# dev_board.net
KiCad netlist of a schematic drawn in EAGLE
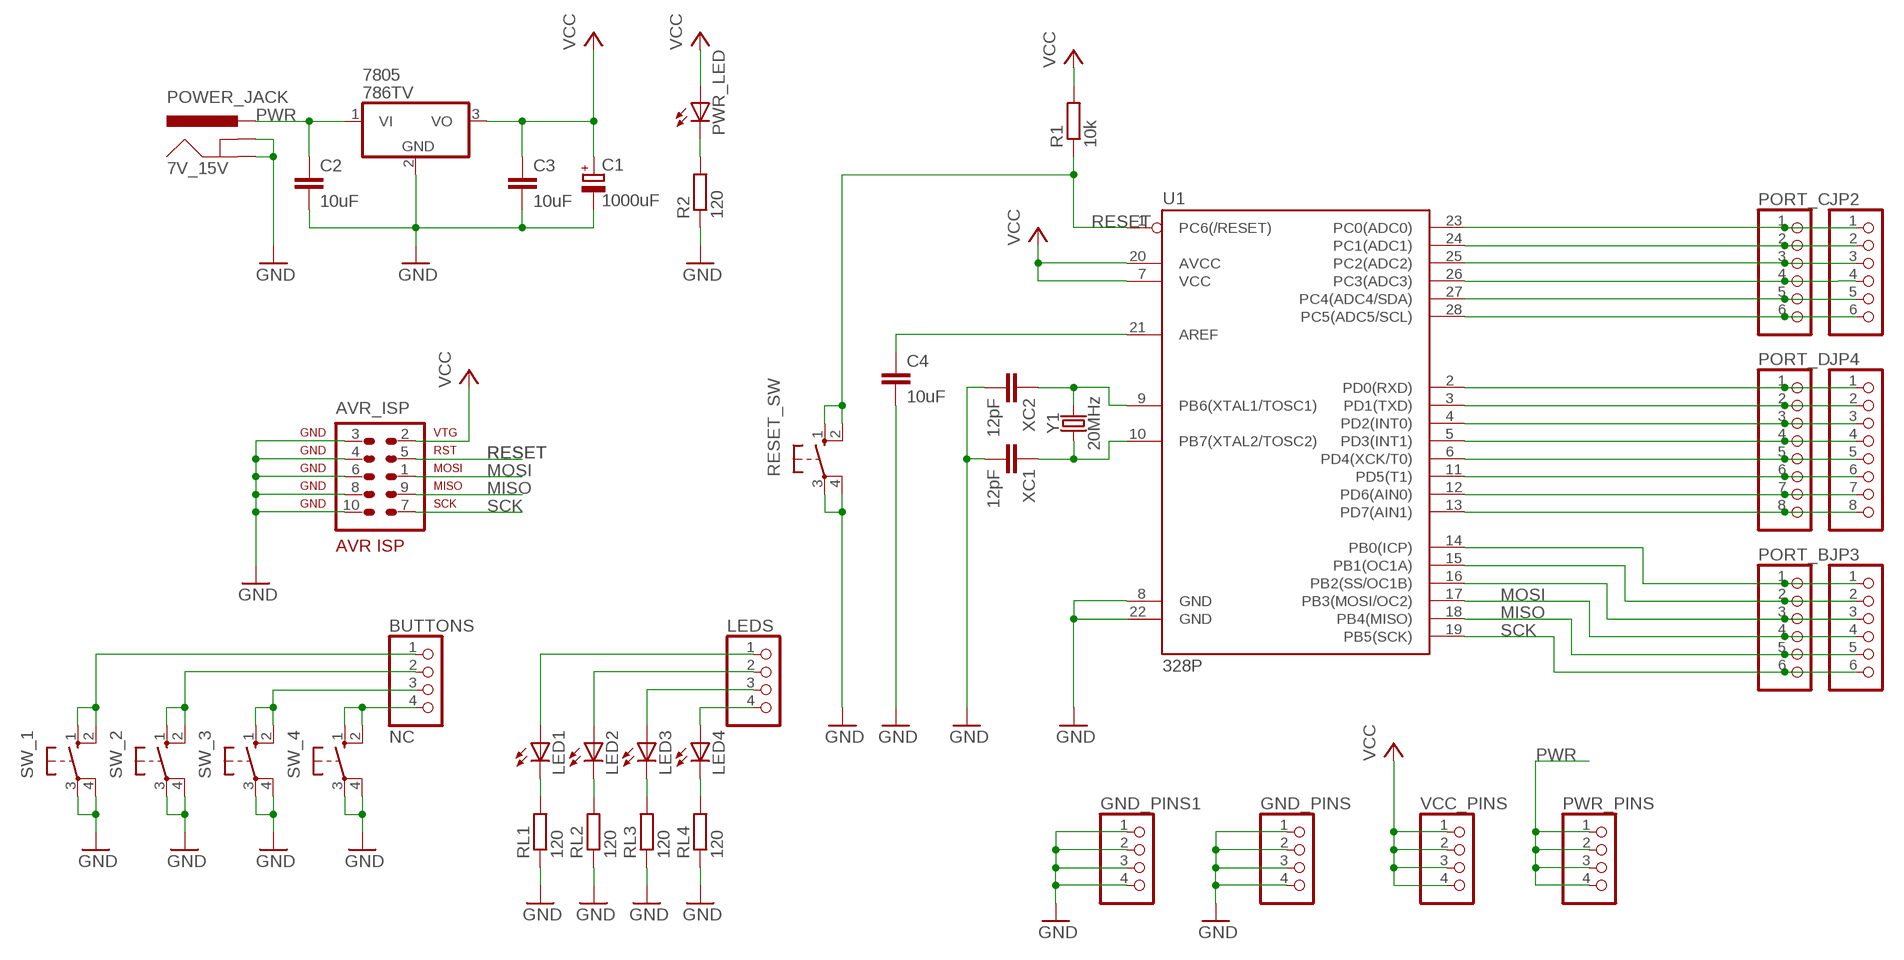
[diagram p0: schematic, sheet 1]

(export (version "E")
  (design (tool "Eeschema 10.0.6"))
  (components
    (comp (ref "7V_15V")
      (value "POWER_JACK")
      (footprint "eagle-import:POWER_JACK_PTH")
      (libsource (lib "eagle-import") (part "POWER_JACK"))
    )
    (comp (ref "7805")
      (value "786TV")
      (footprint "eagle-import:TO220V")
      (libsource (lib "eagle-import") (part "78TV6"))
    )
    (comp (ref "AVR_ISP")
      (value "AVR-ISP-10")
      (footprint "eagle-import:AVR-ISP-10")
      (libsource (lib "eagle-import") (part "AVR-ISP-10"))
    )
    (comp (ref "BUTTONS")
      (value "NC")
      (footprint "eagle-import:1X04")
      (libsource (lib "eagle-import") (part "PINHD-1X4"))
    )
    (comp (ref "C1")
      (value "1000uF")
      (footprint "eagle-import:E3,5-10")
      (libsource (lib "eagle-import") (part "CPOL-EUE3.5-10"))
    )
    (comp (ref "C2")
      (value "10uF")
      (footprint "eagle-import:C025-025X050")
      (libsource (lib "eagle-import") (part "C-EU025-025X050"))
    )
    (comp (ref "C3")
      (value "10uF")
      (footprint "eagle-import:C025-025X050")
      (libsource (lib "eagle-import") (part "C-EU025-025X050"))
    )
    (comp (ref "C4")
      (value "10uF")
      (footprint "eagle-import:C025-025X050")
      (libsource (lib "eagle-import") (part "C-EU025-025X050"))
    )
    (comp (ref "GND_PINS")
      (value "PINHD-1X4")
      (footprint "eagle-import:1X04")
      (libsource (lib "eagle-import") (part "PINHD-1X4"))
    )
    (comp (ref "GND_PINS1")
      (value "PINHD-1X4")
      (footprint "eagle-import:1X04")
      (libsource (lib "eagle-import") (part "PINHD-1X4"))
    )
    (comp (ref "JP2")
      (value "PINHD-1X6")
      (footprint "eagle-import:1X06")
      (libsource (lib "eagle-import") (part "PINHD-1X6"))
    )
    (comp (ref "JP3")
      (value "PINHD-1X6")
      (footprint "eagle-import:1X06")
      (libsource (lib "eagle-import") (part "PINHD-1X6"))
    )
    (comp (ref "JP4")
      (value "PINHD-1X8")
      (footprint "eagle-import:1X08")
      (libsource (lib "eagle-import") (part "PINHD-1X8"))
    )
    (comp (ref "LED1")
      (value "LED5MM")
      (footprint "eagle-import:LED5MM")
      (libsource (lib "eagle-import") (part "LED5MM"))
    )
    (comp (ref "LED2")
      (value "LED5MM")
      (footprint "eagle-import:LED5MM")
      (libsource (lib "eagle-import") (part "LED5MM"))
    )
    (comp (ref "LED3")
      (value "LED5MM")
      (footprint "eagle-import:LED5MM")
      (libsource (lib "eagle-import") (part "LED5MM"))
    )
    (comp (ref "LED4")
      (value "LED5MM")
      (footprint "eagle-import:LED5MM")
      (libsource (lib "eagle-import") (part "LED5MM"))
    )
    (comp (ref "LEDS")
      (value "PINHD-1X4")
      (footprint "eagle-import:1X04")
      (libsource (lib "eagle-import") (part "PINHD-1X4"))
    )
    (comp (ref "PORT_B")
      (value "PINHD-1X6")
      (footprint "eagle-import:1X06")
      (libsource (lib "eagle-import") (part "PINHD-1X6"))
    )
    (comp (ref "PORT_C")
      (value "PINHD-1X6")
      (footprint "eagle-import:1X06")
      (libsource (lib "eagle-import") (part "PINHD-1X6"))
    )
    (comp (ref "PORT_D")
      (value "PINHD-1X8")
      (footprint "eagle-import:1X08")
      (libsource (lib "eagle-import") (part "PINHD-1X8"))
    )
    (comp (ref "PWR_LED")
      (value "LED3MM")
      (footprint "eagle-import:LED3MM")
      (libsource (lib "eagle-import") (part "LED3MM"))
    )
    (comp (ref "PWR_PINS")
      (value "PINHD-1X4")
      (footprint "eagle-import:1X04")
      (libsource (lib "eagle-import") (part "PINHD-1X4"))
    )
    (comp (ref "R1")
      (value "10k")
      (footprint "eagle-import:0207_10")
      (libsource (lib "eagle-import") (part "R-EU_0207/10"))
    )
    (comp (ref "R2")
      (value "120")
      (footprint "eagle-import:0207_10")
      (libsource (lib "eagle-import") (part "R-EU_0207/10"))
    )
    (comp (ref "RESET_SW")
      (value "10-XX")
      (footprint "eagle-import:B3F-10XX")
      (fields (field (name "MPN") "B3F-1000"))
      (libsource (lib "eagle-import") (part "10-XX"))
    )
    (comp (ref "RL1")
      (value "120")
      (footprint "eagle-import:0207_10")
      (libsource (lib "eagle-import") (part "R-EU_0207/10"))
    )
    (comp (ref "RL2")
      (value "120")
      (footprint "eagle-import:0207_10")
      (libsource (lib "eagle-import") (part "R-EU_0207/10"))
    )
    (comp (ref "RL3")
      (value "120")
      (footprint "eagle-import:0207_10")
      (libsource (lib "eagle-import") (part "R-EU_0207/10"))
    )
    (comp (ref "RL4")
      (value "120")
      (footprint "eagle-import:0207_10")
      (libsource (lib "eagle-import") (part "R-EU_0207/10"))
    )
    (comp (ref "SW_1")
      (value "10-XX")
      (footprint "eagle-import:B3F-10XX")
      (fields (field (name "MPN") "B3F-1000"))
      (libsource (lib "eagle-import") (part "10-XX"))
    )
    (comp (ref "SW_2")
      (value "10-XX")
      (footprint "eagle-import:B3F-10XX")
      (fields (field (name "MPN") "B3F-1000"))
      (libsource (lib "eagle-import") (part "10-XX"))
    )
    (comp (ref "SW_3")
      (value "10-XX")
      (footprint "eagle-import:B3F-10XX")
      (fields (field (name "MPN") "B3F-1000"))
      (libsource (lib "eagle-import") (part "10-XX"))
    )
    (comp (ref "SW_4")
      (value "10-XX")
      (footprint "eagle-import:B3F-10XX")
      (fields (field (name "MPN") "B3F-1000"))
      (libsource (lib "eagle-import") (part "10-XX"))
    )
    (comp (ref "U1")
      (value "328P")
      (footprint "eagle-import:DIP28")
      (libsource (lib "eagle-import") (part "ATMEGA328P_PDIP"))
    )
    (comp (ref "VCC_PINS")
      (value "PINHD-1X4")
      (footprint "eagle-import:1X04")
      (libsource (lib "eagle-import") (part "PINHD-1X4"))
    )
    (comp (ref "XC1")
      (value "12pF")
      (footprint "eagle-import:C025-025X050")
      (libsource (lib "eagle-import") (part "C-EU025-025X050"))
    )
    (comp (ref "XC2")
      (value "12pF")
      (footprint "eagle-import:C025-025X050")
      (libsource (lib "eagle-import") (part "C-EU025-025X050"))
    )
    (comp (ref "Y1")
      (value "20MHz")
      (footprint "eagle-import:HC49US")
      (libsource (lib "eagle-import") (part "CRYSTALPTH-HC49US"))
    )
  )
  (nets
    (net (code "1") (name "/MISO") (class "Default")
      (node (ref "AVR_ISP") (pin "9") (pinfunction "9_9") (pintype "passive"))
      (node (ref "JP3") (pin "5") (pinfunction "5_5") (pintype "passive"))
      (node (ref "PORT_B") (pin "5") (pinfunction "5_5") (pintype "passive"))
      (node (ref "U1") (pin "18") (pinfunction "PB4(MISO)_18") (pintype "bidirectional"))
    )
    (net (code "2") (name "/MOSI") (class "Default")
      (node (ref "AVR_ISP") (pin "1") (pinfunction "1_1") (pintype "passive"))
      (node (ref "JP3") (pin "4") (pinfunction "4_4") (pintype "passive"))
      (node (ref "PORT_B") (pin "4") (pinfunction "4_4") (pintype "passive"))
      (node (ref "U1") (pin "17") (pinfunction "PB3(MOSI/OC2)_17") (pintype "bidirectional"))
    )
    (net (code "3") (name "/PWR") (class "Default")
      (node (ref "7805") (pin "1") (pinfunction "VI_1") (pintype "input"))
      (node (ref "7V_15V") (pin "PWR") (pinfunction "PWR_PWR") (pintype "bidirectional"))
      (node (ref "C2") (pin "1") (pinfunction "1_1") (pintype "passive"))
      (node (ref "PWR_PINS") (pin "1") (pinfunction "1_1") (pintype "passive"))
      (node (ref "PWR_PINS") (pin "2") (pinfunction "2_2") (pintype "passive"))
      (node (ref "PWR_PINS") (pin "3") (pinfunction "3_3") (pintype "passive"))
      (node (ref "PWR_PINS") (pin "4") (pinfunction "4_4") (pintype "passive"))
    )
    (net (code "4") (name "/RESET") (class "Default")
      (node (ref "AVR_ISP") (pin "5") (pinfunction "5_5") (pintype "passive"))
      (node (ref "R1") (pin "1") (pinfunction "1_1") (pintype "passive"))
      (node (ref "RESET_SW") (pin "1") (pinfunction "S_1") (pintype "passive"))
      (node (ref "RESET_SW") (pin "2") (pinfunction "S1_2") (pintype "passive"))
      (node (ref "U1") (pin "1") (pinfunction "PC6(/RESET)_1") (pintype "bidirectional"))
    )
    (net (code "5") (name "/SCK") (class "Default")
      (node (ref "AVR_ISP") (pin "7") (pinfunction "7_7") (pintype "passive"))
      (node (ref "JP3") (pin "6") (pinfunction "6_6") (pintype "passive"))
      (node (ref "PORT_B") (pin "6") (pinfunction "6_6") (pintype "passive"))
      (node (ref "U1") (pin "19") (pinfunction "PB5(SCK)_19") (pintype "bidirectional"))
    )
    (net (code "6") (name "GND") (class "Default")
      (node (ref "7805") (pin "2") (pinfunction "GND_2") (pintype "passive"))
      (node (ref "7V_15V") (pin "GND") (pinfunction "GND_GND") (pintype "bidirectional"))
      (node (ref "7V_15V") (pin "GNDBREAK") (pinfunction "GNDBREAK_GNDBREAK") (pintype "bidirectional"))
      (node (ref "AVR_ISP") (pin "10") (pinfunction "10_10") (pintype "passive"))
      (node (ref "AVR_ISP") (pin "3") (pinfunction "3_3") (pintype "passive"))
      (node (ref "AVR_ISP") (pin "4") (pinfunction "4_4") (pintype "passive"))
      (node (ref "AVR_ISP") (pin "6") (pinfunction "6_6") (pintype "passive"))
      (node (ref "AVR_ISP") (pin "8") (pinfunction "8_8") (pintype "passive"))
      (node (ref "C1") (pin "-") (pinfunction "-_-") (pintype "passive"))
      (node (ref "C2") (pin "2") (pinfunction "2_2") (pintype "passive"))
      (node (ref "C3") (pin "2") (pinfunction "2_2") (pintype "passive"))
      (node (ref "C4") (pin "2") (pinfunction "2_2") (pintype "passive"))
      (node (ref "GND_PINS") (pin "1") (pinfunction "1_1") (pintype "passive"))
      (node (ref "GND_PINS") (pin "2") (pinfunction "2_2") (pintype "passive"))
      (node (ref "GND_PINS") (pin "3") (pinfunction "3_3") (pintype "passive"))
      (node (ref "GND_PINS") (pin "4") (pinfunction "4_4") (pintype "passive"))
      (node (ref "GND_PINS1") (pin "1") (pinfunction "1_1") (pintype "passive"))
      (node (ref "GND_PINS1") (pin "2") (pinfunction "2_2") (pintype "passive"))
      (node (ref "GND_PINS1") (pin "3") (pinfunction "3_3") (pintype "passive"))
      (node (ref "GND_PINS1") (pin "4") (pinfunction "4_4") (pintype "passive"))
      (node (ref "R2") (pin "1") (pinfunction "1_1") (pintype "passive"))
      (node (ref "RESET_SW") (pin "3") (pinfunction "P_3") (pintype "passive"))
      (node (ref "RESET_SW") (pin "4") (pinfunction "P1_4") (pintype "passive"))
      (node (ref "RL1") (pin "1") (pinfunction "1_1") (pintype "passive"))
      (node (ref "RL2") (pin "1") (pinfunction "1_1") (pintype "passive"))
      (node (ref "RL3") (pin "1") (pinfunction "1_1") (pintype "passive"))
      (node (ref "RL4") (pin "1") (pinfunction "1_1") (pintype "passive"))
      (node (ref "SW_1") (pin "3") (pinfunction "P_3") (pintype "passive"))
      (node (ref "SW_1") (pin "4") (pinfunction "P1_4") (pintype "passive"))
      (node (ref "SW_2") (pin "3") (pinfunction "P_3") (pintype "passive"))
      (node (ref "SW_2") (pin "4") (pinfunction "P1_4") (pintype "passive"))
      (node (ref "SW_3") (pin "3") (pinfunction "P_3") (pintype "passive"))
      (node (ref "SW_3") (pin "4") (pinfunction "P1_4") (pintype "passive"))
      (node (ref "SW_4") (pin "3") (pinfunction "P_3") (pintype "passive"))
      (node (ref "SW_4") (pin "4") (pinfunction "P1_4") (pintype "passive"))
      (node (ref "U1") (pin "22") (pinfunction "GND_22") (pintype "bidirectional"))
      (node (ref "U1") (pin "8") (pinfunction "GND_8") (pintype "bidirectional"))
      (node (ref "XC1") (pin "2") (pinfunction "2_2") (pintype "passive"))
      (node (ref "XC2") (pin "2") (pinfunction "2_2") (pintype "passive"))
    )
    (net (code "7") (name "Net-(LED1-C)") (class "Default")
      (node (ref "LED1") (pin "K") (pinfunction "C_K") (pintype "passive"))
      (node (ref "RL1") (pin "2") (pinfunction "2_2") (pintype "passive"))
    )
    (net (code "8") (name "Net-(LED1-PadA)") (class "Default")
      (node (ref "LED1") (pin "A") (pinfunction "A_A") (pintype "passive"))
      (node (ref "LEDS") (pin "1") (pinfunction "1_1") (pintype "passive"))
    )
    (net (code "9") (name "Net-(LED2-C)") (class "Default")
      (node (ref "LED2") (pin "K") (pinfunction "C_K") (pintype "passive"))
      (node (ref "RL2") (pin "2") (pinfunction "2_2") (pintype "passive"))
    )
    (net (code "10") (name "Net-(LED2-PadA)") (class "Default")
      (node (ref "LED2") (pin "A") (pinfunction "A_A") (pintype "passive"))
      (node (ref "LEDS") (pin "2") (pinfunction "2_2") (pintype "passive"))
    )
    (net (code "11") (name "Net-(LED3-C)") (class "Default")
      (node (ref "LED3") (pin "K") (pinfunction "C_K") (pintype "passive"))
      (node (ref "RL3") (pin "2") (pinfunction "2_2") (pintype "passive"))
    )
    (net (code "12") (name "Net-(LED3-PadA)") (class "Default")
      (node (ref "LED3") (pin "A") (pinfunction "A_A") (pintype "passive"))
      (node (ref "LEDS") (pin "3") (pinfunction "3_3") (pintype "passive"))
    )
    (net (code "13") (name "Net-(LED4-C)") (class "Default")
      (node (ref "LED4") (pin "K") (pinfunction "C_K") (pintype "passive"))
      (node (ref "RL4") (pin "2") (pinfunction "2_2") (pintype "passive"))
    )
    (net (code "14") (name "Net-(LED4-PadA)") (class "Default")
      (node (ref "LED4") (pin "A") (pinfunction "A_A") (pintype "passive"))
      (node (ref "LEDS") (pin "4") (pinfunction "4_4") (pintype "passive"))
    )
    (net (code "15") (name "Net-(PWR_LED-C)") (class "Default")
      (node (ref "PWR_LED") (pin "K") (pinfunction "C_K") (pintype "passive"))
      (node (ref "R2") (pin "2") (pinfunction "2_2") (pintype "passive"))
    )
    (net (code "16") (name "Net-(SW_1-S)") (class "Default")
      (node (ref "BUTTONS") (pin "1") (pinfunction "1_1") (pintype "passive"))
      (node (ref "SW_1") (pin "1") (pinfunction "S_1") (pintype "passive"))
      (node (ref "SW_1") (pin "2") (pinfunction "S1_2") (pintype "passive"))
    )
    (net (code "17") (name "Net-(SW_2-S)") (class "Default")
      (node (ref "BUTTONS") (pin "2") (pinfunction "2_2") (pintype "passive"))
      (node (ref "SW_2") (pin "1") (pinfunction "S_1") (pintype "passive"))
      (node (ref "SW_2") (pin "2") (pinfunction "S1_2") (pintype "passive"))
    )
    (net (code "18") (name "Net-(SW_3-S)") (class "Default")
      (node (ref "BUTTONS") (pin "3") (pinfunction "3_3") (pintype "passive"))
      (node (ref "SW_3") (pin "1") (pinfunction "S_1") (pintype "passive"))
      (node (ref "SW_3") (pin "2") (pinfunction "S1_2") (pintype "passive"))
    )
    (net (code "19") (name "Net-(SW_4-S)") (class "Default")
      (node (ref "BUTTONS") (pin "4") (pinfunction "4_4") (pintype "passive"))
      (node (ref "SW_4") (pin "1") (pinfunction "S_1") (pintype "passive"))
      (node (ref "SW_4") (pin "2") (pinfunction "S1_2") (pintype "passive"))
    )
    (net (code "20") (name "Net-(U1-AREF)") (class "Default")
      (node (ref "C4") (pin "1") (pinfunction "1_1") (pintype "passive"))
      (node (ref "U1") (pin "21") (pinfunction "AREF_21") (pintype "bidirectional"))
    )
    (net (code "21") (name "Net-(U1-PB0(ICP))") (class "Default")
      (node (ref "JP3") (pin "1") (pinfunction "1_1") (pintype "passive"))
      (node (ref "PORT_B") (pin "1") (pinfunction "1_1") (pintype "passive"))
      (node (ref "U1") (pin "14") (pinfunction "PB0(ICP)_14") (pintype "bidirectional"))
    )
    (net (code "22") (name "Net-(U1-PB1(OC1A))") (class "Default")
      (node (ref "JP3") (pin "2") (pinfunction "2_2") (pintype "passive"))
      (node (ref "PORT_B") (pin "2") (pinfunction "2_2") (pintype "passive"))
      (node (ref "U1") (pin "15") (pinfunction "PB1(OC1A)_15") (pintype "bidirectional"))
    )
    (net (code "23") (name "Net-(U1-PB2(SS{slash}OC1B))") (class "Default")
      (node (ref "JP3") (pin "3") (pinfunction "3_3") (pintype "passive"))
      (node (ref "PORT_B") (pin "3") (pinfunction "3_3") (pintype "passive"))
      (node (ref "U1") (pin "16") (pinfunction "PB2(SS/OC1B)_16") (pintype "bidirectional"))
    )
    (net (code "24") (name "Net-(U1-PB6(XTAL1{slash}TOSC1))") (class "Default")
      (node (ref "U1") (pin "9") (pinfunction "PB6(XTAL1/TOSC1)_9") (pintype "bidirectional"))
      (node (ref "XC2") (pin "1") (pinfunction "1_1") (pintype "passive"))
      (node (ref "Y1") (pin "2") (pinfunction "2_2") (pintype "passive"))
    )
    (net (code "25") (name "Net-(U1-PB7(XTAL2{slash}TOSC2))") (class "Default")
      (node (ref "U1") (pin "10") (pinfunction "PB7(XTAL2/TOSC2)_10") (pintype "bidirectional"))
      (node (ref "XC1") (pin "1") (pinfunction "1_1") (pintype "passive"))
      (node (ref "Y1") (pin "1") (pinfunction "1_1") (pintype "passive"))
    )
    (net (code "26") (name "Net-(U1-PC0(ADC0))") (class "Default")
      (node (ref "JP2") (pin "1") (pinfunction "1_1") (pintype "passive"))
      (node (ref "PORT_C") (pin "1") (pinfunction "1_1") (pintype "passive"))
      (node (ref "U1") (pin "23") (pinfunction "PC0(ADC0)_23") (pintype "bidirectional"))
    )
    (net (code "27") (name "Net-(U1-PC1(ADC1))") (class "Default")
      (node (ref "JP2") (pin "2") (pinfunction "2_2") (pintype "passive"))
      (node (ref "PORT_C") (pin "2") (pinfunction "2_2") (pintype "passive"))
      (node (ref "U1") (pin "24") (pinfunction "PC1(ADC1)_24") (pintype "bidirectional"))
    )
    (net (code "28") (name "Net-(U1-PC2(ADC2))") (class "Default")
      (node (ref "JP2") (pin "3") (pinfunction "3_3") (pintype "passive"))
      (node (ref "PORT_C") (pin "3") (pinfunction "3_3") (pintype "passive"))
      (node (ref "U1") (pin "25") (pinfunction "PC2(ADC2)_25") (pintype "bidirectional"))
    )
    (net (code "29") (name "Net-(U1-PC3(ADC3))") (class "Default")
      (node (ref "JP2") (pin "4") (pinfunction "4_4") (pintype "passive"))
      (node (ref "PORT_C") (pin "4") (pinfunction "4_4") (pintype "passive"))
      (node (ref "U1") (pin "26") (pinfunction "PC3(ADC3)_26") (pintype "bidirectional"))
    )
    (net (code "30") (name "Net-(U1-PC4(ADC4{slash}SDA))") (class "Default")
      (node (ref "JP2") (pin "5") (pinfunction "5_5") (pintype "passive"))
      (node (ref "PORT_C") (pin "5") (pinfunction "5_5") (pintype "passive"))
      (node (ref "U1") (pin "27") (pinfunction "PC4(ADC4/SDA)_27") (pintype "bidirectional"))
    )
    (net (code "31") (name "Net-(U1-PC5(ADC5{slash}SCL))") (class "Default")
      (node (ref "JP2") (pin "6") (pinfunction "6_6") (pintype "passive"))
      (node (ref "PORT_C") (pin "6") (pinfunction "6_6") (pintype "passive"))
      (node (ref "U1") (pin "28") (pinfunction "PC5(ADC5/SCL)_28") (pintype "bidirectional"))
    )
    (net (code "32") (name "Net-(U1-PD0(RXD))") (class "Default")
      (node (ref "JP4") (pin "1") (pinfunction "1_1") (pintype "passive"))
      (node (ref "PORT_D") (pin "1") (pinfunction "1_1") (pintype "passive"))
      (node (ref "U1") (pin "2") (pinfunction "PD0(RXD)_2") (pintype "bidirectional"))
    )
    (net (code "33") (name "Net-(U1-PD1(TXD))") (class "Default")
      (node (ref "JP4") (pin "2") (pinfunction "2_2") (pintype "passive"))
      (node (ref "PORT_D") (pin "2") (pinfunction "2_2") (pintype "passive"))
      (node (ref "U1") (pin "3") (pinfunction "PD1(TXD)_3") (pintype "bidirectional"))
    )
    (net (code "34") (name "Net-(U1-PD2(INT0))") (class "Default")
      (node (ref "JP4") (pin "3") (pinfunction "3_3") (pintype "passive"))
      (node (ref "PORT_D") (pin "3") (pinfunction "3_3") (pintype "passive"))
      (node (ref "U1") (pin "4") (pinfunction "PD2(INT0)_4") (pintype "bidirectional"))
    )
    (net (code "35") (name "Net-(U1-PD3(INT1))") (class "Default")
      (node (ref "JP4") (pin "4") (pinfunction "4_4") (pintype "passive"))
      (node (ref "PORT_D") (pin "4") (pinfunction "4_4") (pintype "passive"))
      (node (ref "U1") (pin "5") (pinfunction "PD3(INT1)_5") (pintype "bidirectional"))
    )
    (net (code "36") (name "Net-(U1-PD4(XCK{slash}T0))") (class "Default")
      (node (ref "JP4") (pin "5") (pinfunction "5_5") (pintype "passive"))
      (node (ref "PORT_D") (pin "5") (pinfunction "5_5") (pintype "passive"))
      (node (ref "U1") (pin "6") (pinfunction "PD4(XCK/T0)_6") (pintype "bidirectional"))
    )
    (net (code "37") (name "Net-(U1-PD5(T1))") (class "Default")
      (node (ref "JP4") (pin "6") (pinfunction "6_6") (pintype "passive"))
      (node (ref "PORT_D") (pin "6") (pinfunction "6_6") (pintype "passive"))
      (node (ref "U1") (pin "11") (pinfunction "PD5(T1)_11") (pintype "bidirectional"))
    )
    (net (code "38") (name "Net-(U1-PD6(AIN0))") (class "Default")
      (node (ref "JP4") (pin "7") (pinfunction "7_7") (pintype "passive"))
      (node (ref "PORT_D") (pin "7") (pinfunction "7_7") (pintype "passive"))
      (node (ref "U1") (pin "12") (pinfunction "PD6(AIN0)_12") (pintype "bidirectional"))
    )
    (net (code "39") (name "Net-(U1-PD7(AIN1))") (class "Default")
      (node (ref "JP4") (pin "8") (pinfunction "8_8") (pintype "passive"))
      (node (ref "PORT_D") (pin "8") (pinfunction "8_8") (pintype "passive"))
      (node (ref "U1") (pin "13") (pinfunction "PD7(AIN1)_13") (pintype "bidirectional"))
    )
    (net (code "40") (name "VCC") (class "Default")
      (node (ref "7805") (pin "3") (pinfunction "VO_3") (pintype "passive"))
      (node (ref "AVR_ISP") (pin "2") (pinfunction "2_2") (pintype "passive"))
      (node (ref "C1") (pin "+") (pinfunction "+_+") (pintype "passive"))
      (node (ref "C3") (pin "1") (pinfunction "1_1") (pintype "passive"))
      (node (ref "PWR_LED") (pin "A") (pinfunction "A_A") (pintype "passive"))
      (node (ref "R1") (pin "2") (pinfunction "2_2") (pintype "passive"))
      (node (ref "U1") (pin "20") (pinfunction "AVCC_20") (pintype "bidirectional"))
      (node (ref "U1") (pin "7") (pinfunction "VCC_7") (pintype "bidirectional"))
      (node (ref "VCC_PINS") (pin "1") (pinfunction "1_1") (pintype "passive"))
      (node (ref "VCC_PINS") (pin "2") (pinfunction "2_2") (pintype "passive"))
      (node (ref "VCC_PINS") (pin "3") (pinfunction "3_3") (pintype "passive"))
      (node (ref "VCC_PINS") (pin "4") (pinfunction "4_4") (pintype "passive"))
    )
  )
)
